# v1_0.net
KiCad netlist of a schematic drawn in EAGLE
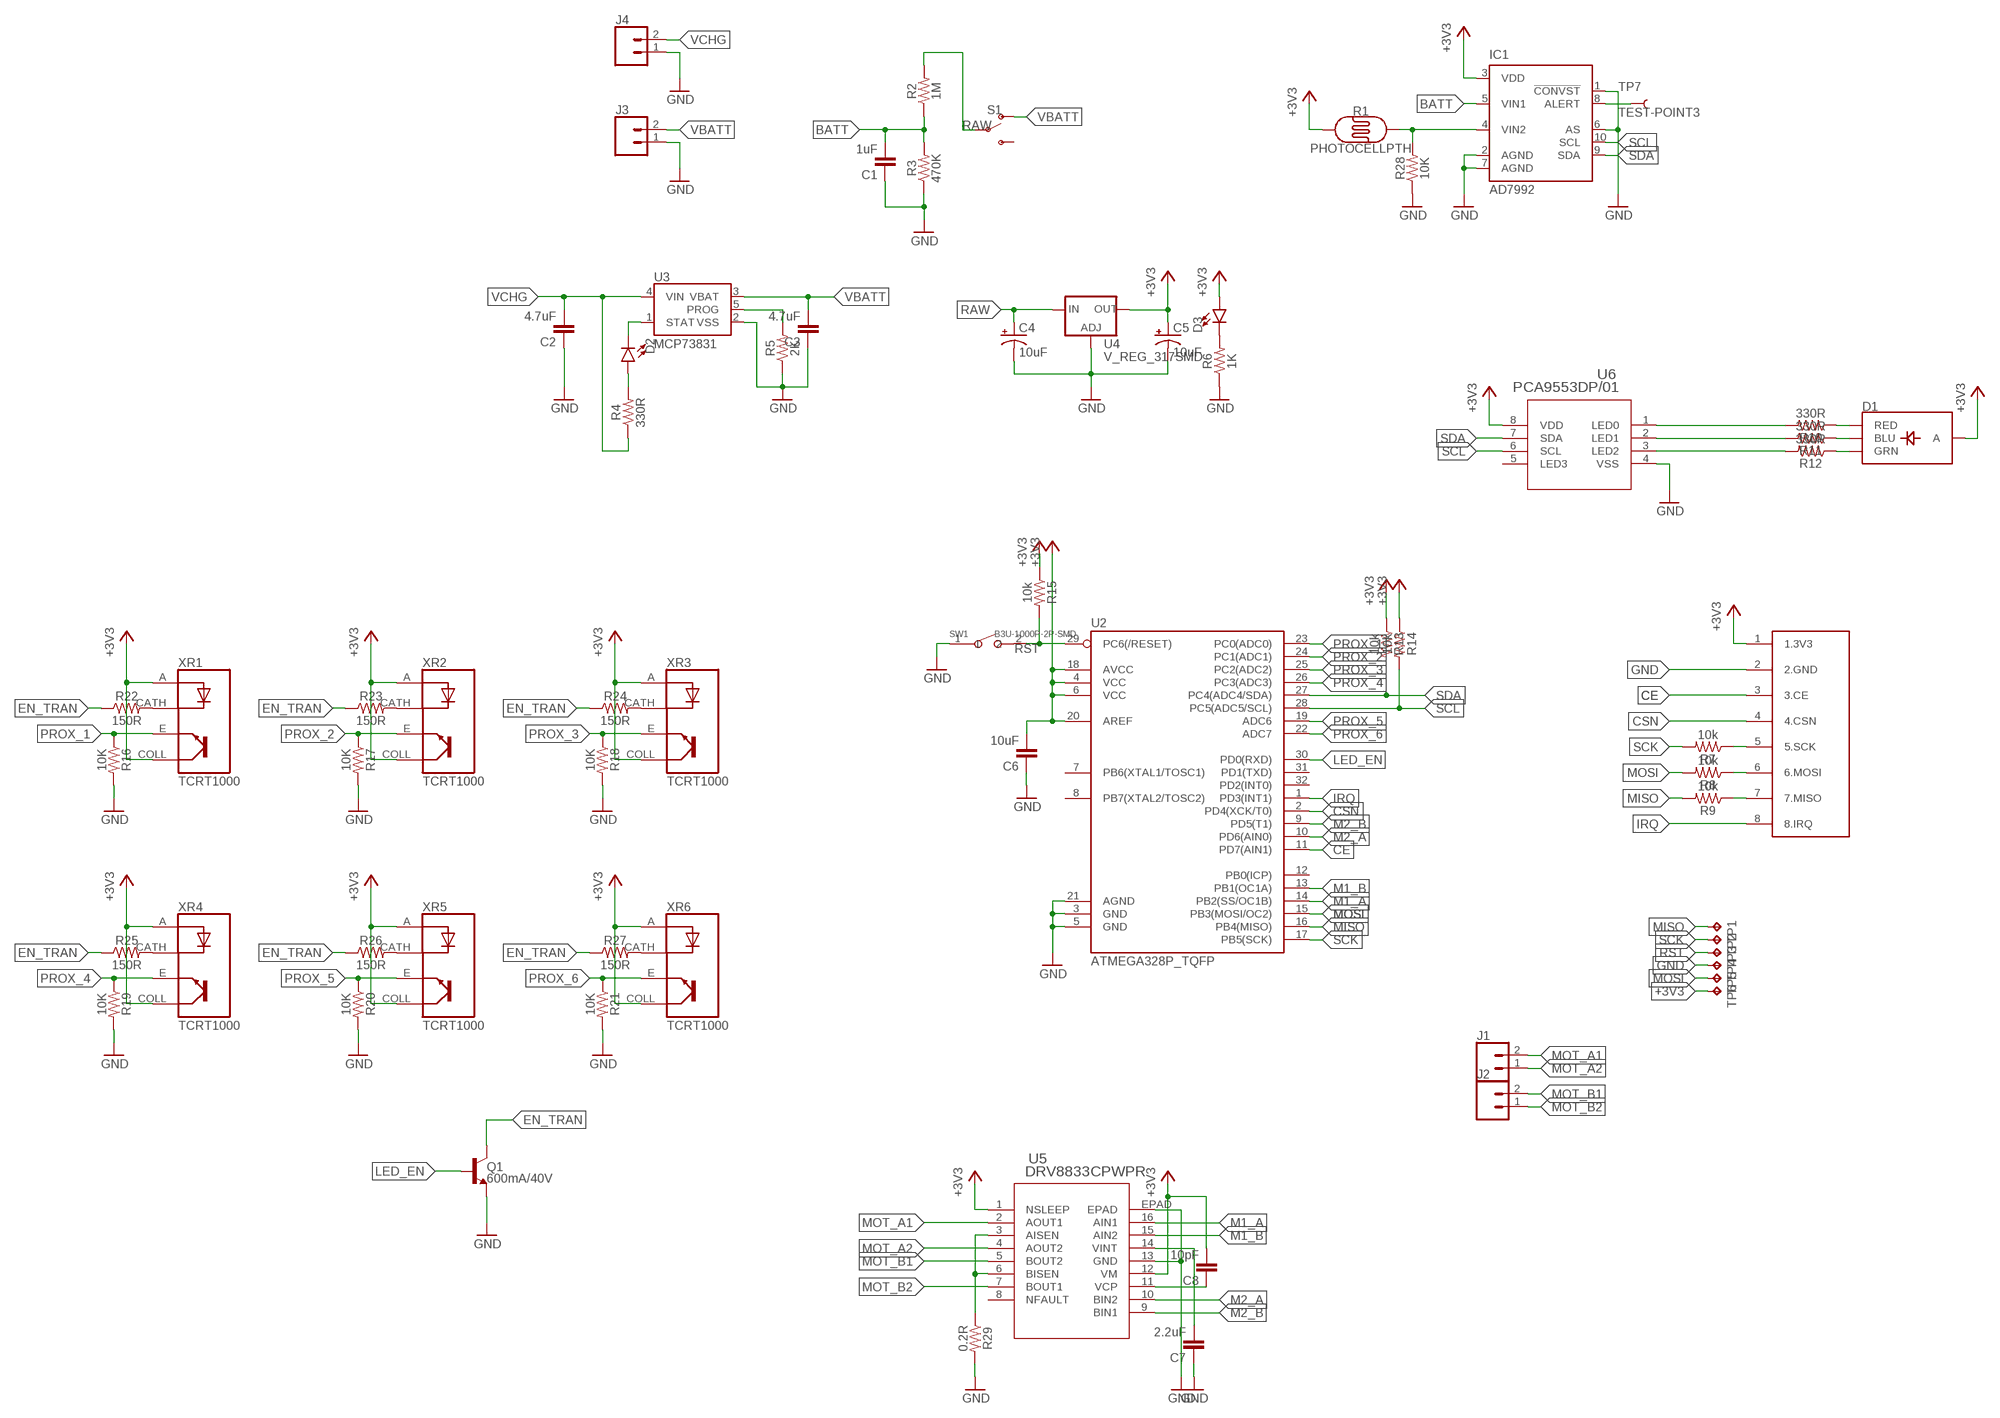
[diagram p0: schematic, sheet 1]

(export (version "E")
  (design (tool "Eeschema 10.0.6"))
  (components
    (comp (ref "C1")
      (value "1uF")
      (footprint "eagle-import:C0603")
      (libsource (lib "eagle-import") (part "C-EUC0603"))
    )
    (comp (ref "C2")
      (value "4.7uF")
      (footprint "eagle-import:C0603")
      (libsource (lib "eagle-import") (part "C-EUC0603"))
    )
    (comp (ref "C3")
      (value "4.7uF")
      (footprint "eagle-import:C0603")
      (libsource (lib "eagle-import") (part "C-EUC0603"))
    )
    (comp (ref "C4")
      (value "10uF")
      (footprint "eagle-import:EIA3216")
      (libsource (lib "eagle-import") (part "10UF-POLAR-EIA3216-16V-10%(TANT)"))
    )
    (comp (ref "C5")
      (value "10uF")
      (footprint "eagle-import:EIA3216")
      (libsource (lib "eagle-import") (part "10UF-POLAR-EIA3216-16V-10%(TANT)"))
    )
    (comp (ref "C6")
      (value "10uF")
      (footprint "eagle-import:C0603")
      (libsource (lib "eagle-import") (part "C-EUC0603"))
    )
    (comp (ref "C7")
      (value "2.2uF")
      (footprint "eagle-import:C0603")
      (libsource (lib "eagle-import") (part "C-EUC0603"))
    )
    (comp (ref "C8")
      (value "10pF")
      (footprint "eagle-import:C0603")
      (libsource (lib "eagle-import") (part "C-EUC0603"))
    )
    (comp (ref "D1")
      (value "LED-RGB-CASMD")
      (footprint "eagle-import:LED-TRICOLOR-SMD")
      (libsource (lib "eagle-import") (part "LED-RGB-CASMD"))
    )
    (comp (ref "D2")
      (value "LED0603")
      (footprint "eagle-import:LED-0603")
      (libsource (lib "eagle-import") (part "LED0603"))
    )
    (comp (ref "D3")
      (value "LED0603")
      (footprint "eagle-import:LED-0603")
      (libsource (lib "eagle-import") (part "LED0603"))
    )
    (comp (ref "IC1")
      (value "AD7992")
      (footprint "eagle-import:MSOP10")
      (fields (field (name "MPN") "AD7992BRMZ-0"))
      (libsource (lib "eagle-import") (part "AD7992"))
    )
    (comp (ref "J1")
      (value "CONN_02")
      (footprint "eagle-import:1X02")
      (libsource (lib "eagle-import") (part "CONN_02"))
    )
    (comp (ref "J2")
      (value "CONN_02")
      (footprint "eagle-import:1X02")
      (libsource (lib "eagle-import") (part "CONN_02"))
    )
    (comp (ref "J3")
      (value "CONN_02")
      (footprint "eagle-import:1X02")
      (libsource (lib "eagle-import") (part "CONN_02"))
    )
    (comp (ref "J4")
      (value "CONN_02")
      (footprint "eagle-import:1X02")
      (libsource (lib "eagle-import") (part "CONN_02"))
    )
    (comp (ref "Q1")
      (value "600mA/40V")
      (footprint "eagle-import:SOT23-3")
      (libsource (lib "eagle-import") (part "TRANS_NPN-MMBT2222AL"))
    )
    (comp (ref "R1")
      (value "PHOTOCELLPTH")
      (footprint "eagle-import:PHOTOCELL")
      (libsource (lib "eagle-import") (part "PHOTOCELLPTH"))
    )
    (comp (ref "R2")
      (value "1M")
      (footprint "eagle-import:0402")
      (libsource (lib "eagle-import") (part "RESISTOR0402"))
    )
    (comp (ref "R3")
      (value "470K")
      (footprint "eagle-import:0402")
      (libsource (lib "eagle-import") (part "RESISTOR0402"))
    )
    (comp (ref "R4")
      (value "330R")
      (footprint "eagle-import:0402")
      (libsource (lib "eagle-import") (part "RESISTOR0402"))
    )
    (comp (ref "R5")
      (value "2K")
      (footprint "eagle-import:0402")
      (libsource (lib "eagle-import") (part "RESISTOR0402"))
    )
    (comp (ref "R6")
      (value "1K")
      (footprint "eagle-import:0402")
      (libsource (lib "eagle-import") (part "RESISTOR0402"))
    )
    (comp (ref "R7")
      (value "10k")
      (footprint "eagle-import:0402")
      (libsource (lib "eagle-import") (part "RESISTOR0402"))
    )
    (comp (ref "R8")
      (value "10k")
      (footprint "eagle-import:0402")
      (libsource (lib "eagle-import") (part "RESISTOR0402"))
    )
    (comp (ref "R9")
      (value "10k")
      (footprint "eagle-import:0402")
      (libsource (lib "eagle-import") (part "RESISTOR0402"))
    )
    (comp (ref "R10")
      (value "330R")
      (footprint "eagle-import:0402")
      (libsource (lib "eagle-import") (part "RESISTOR0402"))
    )
    (comp (ref "R11")
      (value "330R")
      (footprint "eagle-import:0402")
      (libsource (lib "eagle-import") (part "RESISTOR0402"))
    )
    (comp (ref "R12")
      (value "330R")
      (footprint "eagle-import:0402")
      (libsource (lib "eagle-import") (part "RESISTOR0402"))
    )
    (comp (ref "R13")
      (value "10k")
      (footprint "eagle-import:0402")
      (libsource (lib "eagle-import") (part "RESISTOR0402"))
    )
    (comp (ref "R14")
      (value "10k")
      (footprint "eagle-import:0402")
      (libsource (lib "eagle-import") (part "RESISTOR0402"))
    )
    (comp (ref "R15")
      (value "10k")
      (footprint "eagle-import:0402")
      (libsource (lib "eagle-import") (part "RESISTOR0402"))
    )
    (comp (ref "R16")
      (value "10K")
      (footprint "eagle-import:0402")
      (libsource (lib "eagle-import") (part "RESISTOR0402"))
    )
    (comp (ref "R17")
      (value "10K")
      (footprint "eagle-import:0402")
      (libsource (lib "eagle-import") (part "RESISTOR0402"))
    )
    (comp (ref "R18")
      (value "10K")
      (footprint "eagle-import:0402")
      (libsource (lib "eagle-import") (part "RESISTOR0402"))
    )
    (comp (ref "R19")
      (value "10K")
      (footprint "eagle-import:0402")
      (libsource (lib "eagle-import") (part "RESISTOR0402"))
    )
    (comp (ref "R20")
      (value "10K")
      (footprint "eagle-import:0402")
      (libsource (lib "eagle-import") (part "RESISTOR0402"))
    )
    (comp (ref "R21")
      (value "10K")
      (footprint "eagle-import:0402")
      (libsource (lib "eagle-import") (part "RESISTOR0402"))
    )
    (comp (ref "R22")
      (value "150R")
      (footprint "eagle-import:0402")
      (libsource (lib "eagle-import") (part "RESISTOR0402"))
    )
    (comp (ref "R23")
      (value "150R")
      (footprint "eagle-import:0402")
      (libsource (lib "eagle-import") (part "RESISTOR0402"))
    )
    (comp (ref "R24")
      (value "150R")
      (footprint "eagle-import:0402")
      (libsource (lib "eagle-import") (part "RESISTOR0402"))
    )
    (comp (ref "R25")
      (value "150R")
      (footprint "eagle-import:0402")
      (libsource (lib "eagle-import") (part "RESISTOR0402"))
    )
    (comp (ref "R26")
      (value "150R")
      (footprint "eagle-import:0402")
      (libsource (lib "eagle-import") (part "RESISTOR0402"))
    )
    (comp (ref "R27")
      (value "150R")
      (footprint "eagle-import:0402")
      (libsource (lib "eagle-import") (part "RESISTOR0402"))
    )
    (comp (ref "R28")
      (value "10K")
      (footprint "eagle-import:0402")
      (libsource (lib "eagle-import") (part "RESISTOR0402"))
    )
    (comp (ref "R29")
      (value "0.2R")
      (footprint "eagle-import:0402")
      (libsource (lib "eagle-import") (part "RESISTOR0402"))
    )
    (comp (ref "S1")
      (value "SWITCH-SPDT-SMD-RIGHT-ANGLE")
      (footprint "eagle-import:SWITCH_SPST_SMD_A")
      (libsource (lib "eagle-import") (part "SWITCH-SPDT-SMD-RIGHT-ANGLE"))
    )
    (comp (ref "SW1")
      (value "B3U-1000P-2P-SMD")
      (footprint "eagle-import:SW2-2.6-3.0X2.5X1.2+0.4MM")
      (libsource (lib "eagle-import") (part "SMD-BUTTON(2P-3.0X2.5X1.2+0.4MM)-B3U-1000P-2P-SMD"))
    )
    (comp (ref "TP1")
      (value "TPB1,27")
      (footprint "eagle-import:B1,27")
      (libsource (lib "eagle-import") (part "TPB1,27"))
    )
    (comp (ref "TP2")
      (value "TPB1,27")
      (footprint "eagle-import:B1,27")
      (libsource (lib "eagle-import") (part "TPB1,27"))
    )
    (comp (ref "TP3")
      (value "TPB1,27")
      (footprint "eagle-import:B1,27")
      (libsource (lib "eagle-import") (part "TPB1,27"))
    )
    (comp (ref "TP4")
      (value "TPB1,27")
      (footprint "eagle-import:B1,27")
      (libsource (lib "eagle-import") (part "TPB1,27"))
    )
    (comp (ref "TP5")
      (value "TPB1,27")
      (footprint "eagle-import:B1,27")
      (libsource (lib "eagle-import") (part "TPB1,27"))
    )
    (comp (ref "TP6")
      (value "TPB1,27")
      (footprint "eagle-import:B1,27")
      (libsource (lib "eagle-import") (part "TPB1,27"))
    )
    (comp (ref "TP7")
      (value "TEST-POINT3")
      (footprint "eagle-import:PAD.03X.03")
      (libsource (lib "eagle-import") (part "TEST-POINT3"))
    )
    (comp (ref "U$1")
      (value "NRF24L01+")
      (footprint "eagle-import:NRF24L01+")
      (libsource (lib "eagle-import") (part "NRF24L01+"))
    )
    (comp (ref "U2")
      (value "ATMEGA328P_TQFP")
      (footprint "eagle-import:TQFP32-08")
      (libsource (lib "eagle-import") (part "ATMEGA328P_TQFP"))
    )
    (comp (ref "U3")
      (value "MCP73831")
      (footprint "eagle-import:SOT23-5")
      (libsource (lib "eagle-import") (part "MCP73831"))
    )
    (comp (ref "U4")
      (value "V_REG_317SMD")
      (footprint "eagle-import:SOT223")
      (libsource (lib "eagle-import") (part "V_REG_317SMD"))
    )
    (comp (ref "U5")
      (value "DRV8833CPWPR")
      (footprint "eagle-import:PWP16_2P31X2P46")
      (libsource (lib "eagle-import") (part "DRV8833CPWPR"))
    )
    (comp (ref "U6")
      (value "PCA9553DP/01")
      (footprint "eagle-import:SOT505-1")
      (fields (field (name "MANUFACTURER_PART_NUMBER") "PCA9553DP01"))
      (libsource (lib "eagle-import") (part "PCA9553DP/01"))
    )
    (comp (ref "XR1")
      (value "TCRT1000")
      (footprint "eagle-import:XDCR_TCRT1000")
      (fields (field (name "MF") "Vishay"))
      (libsource (lib "eagle-import") (part "TCRT1000"))
    )
    (comp (ref "XR2")
      (value "TCRT1000")
      (footprint "eagle-import:XDCR_TCRT1000")
      (fields (field (name "MF") "Vishay"))
      (libsource (lib "eagle-import") (part "TCRT1000"))
    )
    (comp (ref "XR3")
      (value "TCRT1000")
      (footprint "eagle-import:XDCR_TCRT1000")
      (fields (field (name "MF") "Vishay"))
      (libsource (lib "eagle-import") (part "TCRT1000"))
    )
    (comp (ref "XR4")
      (value "TCRT1000")
      (footprint "eagle-import:XDCR_TCRT1000")
      (fields (field (name "MF") "Vishay"))
      (libsource (lib "eagle-import") (part "TCRT1000"))
    )
    (comp (ref "XR5")
      (value "TCRT1000")
      (footprint "eagle-import:XDCR_TCRT1000")
      (fields (field (name "MF") "Vishay"))
      (libsource (lib "eagle-import") (part "TCRT1000"))
    )
    (comp (ref "XR6")
      (value "TCRT1000")
      (footprint "eagle-import:XDCR_TCRT1000")
      (fields (field (name "MF") "Vishay"))
      (libsource (lib "eagle-import") (part "TCRT1000"))
    )
  )
  (nets
    (net (code "1") (name "+3V3") (class "Default")
      (node (ref "C5") (pin "+") (pinfunction "+_+") (pintype "passive"))
      (node (ref "C6") (pin "2") (pinfunction "2_2") (pintype "passive"))
      (node (ref "C8") (pin "2") (pinfunction "2_2") (pintype "passive"))
      (node (ref "D1") (pin "A") (pinfunction "A_A") (pintype "bidirectional"))
      (node (ref "D3") (pin "A") (pinfunction "A_A") (pintype "passive"))
      (node (ref "IC1") (pin "3") (pinfunction "VDD_3") (pintype "power_in"))
      (node (ref "R1") (pin "1") (pinfunction "P$1_1") (pintype "bidirectional"))
      (node (ref "R13") (pin "1") (pinfunction "1_1") (pintype "passive"))
      (node (ref "R14") (pin "1") (pinfunction "1_1") (pintype "passive"))
      (node (ref "R15") (pin "1") (pinfunction "1_1") (pintype "passive"))
      (node (ref "TP6") (pin "TP") (pinfunction "TP_TP") (pintype "input"))
      (node (ref "U$1") (pin "1") (pinfunction "1.3V3_1") (pintype "bidirectional"))
      (node (ref "U2") (pin "18") (pinfunction "AVCC_18") (pintype "bidirectional"))
      (node (ref "U2") (pin "20") (pinfunction "AREF_20") (pintype "bidirectional"))
      (node (ref "U2") (pin "4") (pinfunction "VCC_4") (pintype "bidirectional"))
      (node (ref "U2") (pin "6") (pinfunction "VCC_6") (pintype "bidirectional"))
      (node (ref "U4") (pin "2") (pinfunction "OUT_2") (pintype "output"))
      (node (ref "U5") (pin "1") (pinfunction "NSLEEP_1") (pintype "input"))
      (node (ref "U5") (pin "12") (pinfunction "VM_12") (pintype "power_in"))
      (node (ref "U6") (pin "8") (pinfunction "VDD_8") (pintype "passive"))
      (node (ref "XR1") (pin "A") (pinfunction "A_A") (pintype "passive"))
      (node (ref "XR1") (pin "COLL") (pinfunction "CO_COLL") (pintype "passive"))
      (node (ref "XR2") (pin "A") (pinfunction "A_A") (pintype "passive"))
      (node (ref "XR2") (pin "COLL") (pinfunction "CO_COLL") (pintype "passive"))
      (node (ref "XR3") (pin "A") (pinfunction "A_A") (pintype "passive"))
      (node (ref "XR3") (pin "COLL") (pinfunction "CO_COLL") (pintype "passive"))
      (node (ref "XR4") (pin "A") (pinfunction "A_A") (pintype "passive"))
      (node (ref "XR4") (pin "COLL") (pinfunction "CO_COLL") (pintype "passive"))
      (node (ref "XR5") (pin "A") (pinfunction "A_A") (pintype "passive"))
      (node (ref "XR5") (pin "COLL") (pinfunction "CO_COLL") (pintype "passive"))
      (node (ref "XR6") (pin "A") (pinfunction "A_A") (pintype "passive"))
      (node (ref "XR6") (pin "COLL") (pinfunction "CO_COLL") (pintype "passive"))
    )
    (net (code "2") (name "BATT") (class "Default")
      (node (ref "C1") (pin "2") (pinfunction "2_2") (pintype "passive"))
      (node (ref "IC1") (pin "5") (pinfunction "VIN1_5") (pintype "input"))
      (node (ref "R2") (pin "1") (pinfunction "1_1") (pintype "passive"))
      (node (ref "R3") (pin "2") (pinfunction "2_2") (pintype "passive"))
    )
    (net (code "3") (name "CE") (class "Default")
      (node (ref "U$1") (pin "3") (pinfunction "3.CE_3") (pintype "bidirectional"))
      (node (ref "U2") (pin "11") (pinfunction "PD7(AIN1)_11") (pintype "bidirectional"))
    )
    (net (code "4") (name "CSN") (class "Default")
      (node (ref "U$1") (pin "4") (pinfunction "4.CSN_4") (pintype "bidirectional"))
      (node (ref "U2") (pin "2") (pinfunction "PD4(XCK/T0)_2") (pintype "bidirectional"))
    )
    (net (code "5") (name "EN_TRAN") (class "Default")
      (node (ref "Q1") (pin "3") (pinfunction "C_3") (pintype "passive"))
      (node (ref "R22") (pin "1") (pinfunction "1_1") (pintype "passive"))
      (node (ref "R23") (pin "1") (pinfunction "1_1") (pintype "passive"))
      (node (ref "R24") (pin "1") (pinfunction "1_1") (pintype "passive"))
      (node (ref "R25") (pin "1") (pinfunction "1_1") (pintype "passive"))
      (node (ref "R26") (pin "1") (pinfunction "1_1") (pintype "passive"))
      (node (ref "R27") (pin "1") (pinfunction "1_1") (pintype "passive"))
    )
    (net (code "6") (name "GND") (class "Default")
      (node (ref "C1") (pin "1") (pinfunction "1_1") (pintype "passive"))
      (node (ref "C2") (pin "1") (pinfunction "1_1") (pintype "passive"))
      (node (ref "C3") (pin "1") (pinfunction "1_1") (pintype "passive"))
      (node (ref "C4") (pin "-") (pinfunction "-_-") (pintype "passive"))
      (node (ref "C5") (pin "-") (pinfunction "-_-") (pintype "passive"))
      (node (ref "C6") (pin "1") (pinfunction "1_1") (pintype "passive"))
      (node (ref "C7") (pin "1") (pinfunction "1_1") (pintype "passive"))
      (node (ref "IC1") (pin "1") (pinfunction "~{CONVST}_1") (pintype "input"))
      (node (ref "IC1") (pin "2") (pinfunction "AGND_2") (pintype "power_in"))
      (node (ref "IC1") (pin "6") (pinfunction "AS_6") (pintype "input"))
      (node (ref "IC1") (pin "7") (pinfunction "AGND_7") (pintype "power_in"))
      (node (ref "J3") (pin "1") (pinfunction "1_1") (pintype "passive"))
      (node (ref "J4") (pin "1") (pinfunction "1_1") (pintype "passive"))
      (node (ref "Q1") (pin "2") (pinfunction "E_2") (pintype "passive"))
      (node (ref "R16") (pin "2") (pinfunction "2_2") (pintype "passive"))
      (node (ref "R17") (pin "2") (pinfunction "2_2") (pintype "passive"))
      (node (ref "R18") (pin "2") (pinfunction "2_2") (pintype "passive"))
      (node (ref "R19") (pin "2") (pinfunction "2_2") (pintype "passive"))
      (node (ref "R20") (pin "2") (pinfunction "2_2") (pintype "passive"))
      (node (ref "R21") (pin "2") (pinfunction "2_2") (pintype "passive"))
      (node (ref "R28") (pin "1") (pinfunction "1_1") (pintype "passive"))
      (node (ref "R29") (pin "2") (pinfunction "2_2") (pintype "passive"))
      (node (ref "R3") (pin "1") (pinfunction "1_1") (pintype "passive"))
      (node (ref "R5") (pin "1") (pinfunction "1_1") (pintype "passive"))
      (node (ref "R6") (pin "1") (pinfunction "1_1") (pintype "passive"))
      (node (ref "SW1") (pin "1") (pinfunction "1_1") (pintype "bidirectional"))
      (node (ref "TP4") (pin "TP") (pinfunction "TP_TP") (pintype "input"))
      (node (ref "U$1") (pin "2") (pinfunction "2.GND_2") (pintype "bidirectional"))
      (node (ref "U2") (pin "21") (pinfunction "AGND_21") (pintype "bidirectional"))
      (node (ref "U2") (pin "3") (pinfunction "GND_3") (pintype "bidirectional"))
      (node (ref "U2") (pin "5") (pinfunction "GND_5") (pintype "bidirectional"))
      (node (ref "U3") (pin "2") (pinfunction "VSS_2") (pintype "power_in"))
      (node (ref "U4") (pin "1") (pinfunction "ADJ_1") (pintype "input"))
      (node (ref "U5") (pin "13") (pinfunction "GND_13") (pintype "power_in"))
      (node (ref "U5") (pin "EPAD") (pinfunction "EPAD_EPAD") (pintype "passive"))
      (node (ref "U6") (pin "4") (pinfunction "VSS_4") (pintype "passive"))
    )
    (net (code "7") (name "IRQ") (class "Default")
      (node (ref "U$1") (pin "8") (pinfunction "8.IRQ_8") (pintype "bidirectional"))
      (node (ref "U2") (pin "1") (pinfunction "PD3(INT1)_1") (pintype "bidirectional"))
    )
    (net (code "8") (name "LED_EN") (class "Default")
      (node (ref "Q1") (pin "1") (pinfunction "B_1") (pintype "passive"))
      (node (ref "U2") (pin "30") (pinfunction "PD0(RXD)_30") (pintype "bidirectional"))
    )
    (net (code "9") (name "M1_A") (class "Default")
      (node (ref "U2") (pin "14") (pinfunction "PB2(SS/OC1B)_14") (pintype "bidirectional"))
      (node (ref "U5") (pin "16") (pinfunction "AIN1_16") (pintype "input"))
    )
    (net (code "10") (name "M1_B") (class "Default")
      (node (ref "U2") (pin "13") (pinfunction "PB1(OC1A)_13") (pintype "bidirectional"))
      (node (ref "U5") (pin "15") (pinfunction "AIN2_15") (pintype "input"))
    )
    (net (code "11") (name "M2_A") (class "Default")
      (node (ref "U2") (pin "10") (pinfunction "PD6(AIN0)_10") (pintype "bidirectional"))
      (node (ref "U5") (pin "10") (pinfunction "BIN2_10") (pintype "input"))
    )
    (net (code "12") (name "M2_B") (class "Default")
      (node (ref "U2") (pin "9") (pinfunction "PD5(T1)_9") (pintype "bidirectional"))
      (node (ref "U5") (pin "9") (pinfunction "BIN1_9") (pintype "input"))
    )
    (net (code "13") (name "MISO") (class "Default")
      (node (ref "R9") (pin "2") (pinfunction "2_2") (pintype "passive"))
      (node (ref "TP1") (pin "TP") (pinfunction "TP_TP") (pintype "input"))
      (node (ref "U2") (pin "16") (pinfunction "PB4(MISO)_16") (pintype "bidirectional"))
    )
    (net (code "14") (name "MOSI") (class "Default")
      (node (ref "R8") (pin "2") (pinfunction "2_2") (pintype "passive"))
      (node (ref "TP5") (pin "TP") (pinfunction "TP_TP") (pintype "input"))
      (node (ref "U2") (pin "15") (pinfunction "PB3(MOSI/OC2)_15") (pintype "bidirectional"))
    )
    (net (code "15") (name "MOT_A1") (class "Default")
      (node (ref "J1") (pin "2") (pinfunction "2_2") (pintype "passive"))
      (node (ref "U5") (pin "2") (pinfunction "AOUT1_2") (pintype "output"))
    )
    (net (code "16") (name "MOT_A2") (class "Default")
      (node (ref "J1") (pin "1") (pinfunction "1_1") (pintype "passive"))
      (node (ref "U5") (pin "4") (pinfunction "AOUT2_4") (pintype "output"))
    )
    (net (code "17") (name "MOT_B1") (class "Default")
      (node (ref "J2") (pin "2") (pinfunction "2_2") (pintype "passive"))
      (node (ref "U5") (pin "5") (pinfunction "BOUT2_5") (pintype "output"))
    )
    (net (code "18") (name "MOT_B2") (class "Default")
      (node (ref "J2") (pin "1") (pinfunction "1_1") (pintype "passive"))
      (node (ref "U5") (pin "7") (pinfunction "BOUT1_7") (pintype "output"))
    )
    (net (code "19") (name "Net-(D1-BLU)") (class "Default")
      (node (ref "D1") (pin "B") (pinfunction "BLU_B") (pintype "bidirectional"))
      (node (ref "R11") (pin "1") (pinfunction "1_1") (pintype "passive"))
    )
    (net (code "20") (name "Net-(D1-GRN)") (class "Default")
      (node (ref "D1") (pin "G") (pinfunction "GRN_G") (pintype "bidirectional"))
      (node (ref "R12") (pin "1") (pinfunction "1_1") (pintype "passive"))
    )
    (net (code "21") (name "Net-(D1-RED)") (class "Default")
      (node (ref "D1") (pin "R") (pinfunction "RED_R") (pintype "bidirectional"))
      (node (ref "R10") (pin "1") (pinfunction "1_1") (pintype "passive"))
    )
    (net (code "22") (name "Net-(D2-PadA)") (class "Default")
      (node (ref "D2") (pin "A") (pinfunction "A_A") (pintype "passive"))
      (node (ref "R4") (pin "2") (pinfunction "2_2") (pintype "passive"))
    )
    (net (code "23") (name "Net-(D3-PadC)") (class "Default")
      (node (ref "D3") (pin "C") (pinfunction "C_C") (pintype "passive"))
      (node (ref "R6") (pin "2") (pinfunction "2_2") (pintype "passive"))
    )
    (net (code "24") (name "Net-(IC1-ALERT)") (class "Default")
      (node (ref "IC1") (pin "8") (pinfunction "ALERT_8") (pintype "output"))
      (node (ref "TP7") (pin "P$1") (pinfunction "1_P$1") (pintype "bidirectional"))
    )
    (net (code "25") (name "Net-(IC1-VIN2)") (class "Default")
      (node (ref "IC1") (pin "4") (pinfunction "VIN2_4") (pintype "input"))
      (node (ref "R1") (pin "2") (pinfunction "P$2_2") (pintype "bidirectional"))
      (node (ref "R28") (pin "2") (pinfunction "2_2") (pintype "passive"))
    )
    (net (code "26") (name "Net-(U$1-5.SCK)") (class "Default")
      (node (ref "R7") (pin "1") (pinfunction "1_1") (pintype "passive"))
      (node (ref "U$1") (pin "5") (pinfunction "5.SCK_5") (pintype "bidirectional"))
    )
    (net (code "27") (name "Net-(U$1-6.MOSI)") (class "Default")
      (node (ref "R8") (pin "1") (pinfunction "1_1") (pintype "passive"))
      (node (ref "U$1") (pin "6") (pinfunction "6.MOSI_6") (pintype "bidirectional"))
    )
    (net (code "28") (name "Net-(U$1-7.MISO)") (class "Default")
      (node (ref "R9") (pin "1") (pinfunction "1_1") (pintype "passive"))
      (node (ref "U$1") (pin "7") (pinfunction "7.MISO_7") (pintype "bidirectional"))
    )
    (net (code "29") (name "Net-(U3-PROG)") (class "Default")
      (node (ref "R5") (pin "2") (pinfunction "2_2") (pintype "passive"))
      (node (ref "U3") (pin "5") (pinfunction "PROG_5") (pintype "input"))
    )
    (net (code "30") (name "Net-(U3-STAT)") (class "Default")
      (node (ref "D2") (pin "C") (pinfunction "C_C") (pintype "passive"))
      (node (ref "U3") (pin "1") (pinfunction "STAT_1") (pintype "output"))
    )
    (net (code "31") (name "Net-(U5-AISEN)") (class "Default")
      (node (ref "R29") (pin "1") (pinfunction "1_1") (pintype "passive"))
      (node (ref "U5") (pin "3") (pinfunction "AISEN_3") (pintype "bidirectional"))
      (node (ref "U5") (pin "6") (pinfunction "BISEN_6") (pintype "bidirectional"))
    )
    (net (code "32") (name "Net-(U5-VCP)") (class "Default")
      (node (ref "C8") (pin "1") (pinfunction "1_1") (pintype "passive"))
      (node (ref "U5") (pin "11") (pinfunction "VCP_11") (pintype "bidirectional"))
    )
    (net (code "33") (name "Net-(U5-VINT)") (class "Default")
      (node (ref "C7") (pin "2") (pinfunction "2_2") (pintype "passive"))
      (node (ref "U5") (pin "14") (pinfunction "VINT_14") (pintype "power_in"))
    )
    (net (code "34") (name "Net-(U6-LED0)") (class "Default")
      (node (ref "R10") (pin "2") (pinfunction "2_2") (pintype "passive"))
      (node (ref "U6") (pin "1") (pinfunction "LED0_1") (pintype "passive"))
    )
    (net (code "35") (name "Net-(U6-LED1)") (class "Default")
      (node (ref "R11") (pin "2") (pinfunction "2_2") (pintype "passive"))
      (node (ref "U6") (pin "2") (pinfunction "LED1_2") (pintype "passive"))
    )
    (net (code "36") (name "Net-(U6-LED2)") (class "Default")
      (node (ref "R12") (pin "2") (pinfunction "2_2") (pintype "passive"))
      (node (ref "U6") (pin "3") (pinfunction "LED2_3") (pintype "passive"))
    )
    (net (code "37") (name "Net-(XR1-C)") (class "Default")
      (node (ref "R22") (pin "2") (pinfunction "2_2") (pintype "passive"))
      (node (ref "XR1") (pin "CATH") (pinfunction "C_CATH") (pintype "passive"))
    )
    (net (code "38") (name "Net-(XR2-C)") (class "Default")
      (node (ref "R23") (pin "2") (pinfunction "2_2") (pintype "passive"))
      (node (ref "XR2") (pin "CATH") (pinfunction "C_CATH") (pintype "passive"))
    )
    (net (code "39") (name "Net-(XR3-C)") (class "Default")
      (node (ref "R24") (pin "2") (pinfunction "2_2") (pintype "passive"))
      (node (ref "XR3") (pin "CATH") (pinfunction "C_CATH") (pintype "passive"))
    )
    (net (code "40") (name "Net-(XR4-C)") (class "Default")
      (node (ref "R25") (pin "2") (pinfunction "2_2") (pintype "passive"))
      (node (ref "XR4") (pin "CATH") (pinfunction "C_CATH") (pintype "passive"))
    )
    (net (code "41") (name "Net-(XR5-C)") (class "Default")
      (node (ref "R26") (pin "2") (pinfunction "2_2") (pintype "passive"))
      (node (ref "XR5") (pin "CATH") (pinfunction "C_CATH") (pintype "passive"))
    )
    (net (code "42") (name "Net-(XR6-C)") (class "Default")
      (node (ref "R27") (pin "2") (pinfunction "2_2") (pintype "passive"))
      (node (ref "XR6") (pin "CATH") (pinfunction "C_CATH") (pintype "passive"))
    )
    (net (code "43") (name "PROX_1") (class "Default")
      (node (ref "R16") (pin "1") (pinfunction "1_1") (pintype "passive"))
      (node (ref "U2") (pin "23") (pinfunction "PC0(ADC0)_23") (pintype "bidirectional"))
      (node (ref "XR1") (pin "E") (pinfunction "E_E") (pintype "passive"))
    )
    (net (code "44") (name "PROX_2") (class "Default")
      (node (ref "R17") (pin "1") (pinfunction "1_1") (pintype "passive"))
      (node (ref "U2") (pin "24") (pinfunction "PC1(ADC1)_24") (pintype "bidirectional"))
      (node (ref "XR2") (pin "E") (pinfunction "E_E") (pintype "passive"))
    )
    (net (code "45") (name "PROX_3") (class "Default")
      (node (ref "R18") (pin "1") (pinfunction "1_1") (pintype "passive"))
      (node (ref "U2") (pin "25") (pinfunction "PC2(ADC2)_25") (pintype "bidirectional"))
      (node (ref "XR3") (pin "E") (pinfunction "E_E") (pintype "passive"))
    )
    (net (code "46") (name "PROX_4") (class "Default")
      (node (ref "R19") (pin "1") (pinfunction "1_1") (pintype "passive"))
      (node (ref "U2") (pin "26") (pinfunction "PC3(ADC3)_26") (pintype "bidirectional"))
      (node (ref "XR4") (pin "E") (pinfunction "E_E") (pintype "passive"))
    )
    (net (code "47") (name "PROX_5") (class "Default")
      (node (ref "R20") (pin "1") (pinfunction "1_1") (pintype "passive"))
      (node (ref "U2") (pin "19") (pinfunction "ADC6_19") (pintype "bidirectional"))
      (node (ref "XR5") (pin "E") (pinfunction "E_E") (pintype "passive"))
    )
    (net (code "48") (name "PROX_6") (class "Default")
      (node (ref "R21") (pin "1") (pinfunction "1_1") (pintype "passive"))
      (node (ref "U2") (pin "22") (pinfunction "ADC7_22") (pintype "bidirectional"))
      (node (ref "XR6") (pin "E") (pinfunction "E_E") (pintype "passive"))
    )
    (net (code "49") (name "RAW") (class "Default")
      (node (ref "C4") (pin "+") (pinfunction "+_+") (pintype "passive"))
      (node (ref "R2") (pin "2") (pinfunction "2_2") (pintype "passive"))
      (node (ref "S1") (pin "2") (pinfunction "P_2") (pintype "passive"))
      (node (ref "U4") (pin "3") (pinfunction "IN_3") (pintype "input"))
    )
    (net (code "50") (name "RST") (class "Default")
      (node (ref "R15") (pin "2") (pinfunction "2_2") (pintype "passive"))
      (node (ref "SW1") (pin "2") (pinfunction "2_2") (pintype "bidirectional"))
      (node (ref "TP3") (pin "TP") (pinfunction "TP_TP") (pintype "input"))
      (node (ref "U2") (pin "29") (pinfunction "PC6(/RESET)_29") (pintype "bidirectional"))
    )
    (net (code "51") (name "SCK") (class "Default")
      (node (ref "R7") (pin "2") (pinfunction "2_2") (pintype "passive"))
      (node (ref "TP2") (pin "TP") (pinfunction "TP_TP") (pintype "input"))
      (node (ref "U2") (pin "17") (pinfunction "PB5(SCK)_17") (pintype "bidirectional"))
    )
    (net (code "52") (name "SCL") (class "Default")
      (node (ref "IC1") (pin "10") (pinfunction "SCL_10") (pintype "input"))
      (node (ref "R14") (pin "2") (pinfunction "2_2") (pintype "passive"))
      (node (ref "U2") (pin "28") (pinfunction "PC5(ADC5/SCL)_28") (pintype "bidirectional"))
      (node (ref "U6") (pin "6") (pinfunction "SCL_6") (pintype "passive"))
    )
    (net (code "53") (name "SDA") (class "Default")
      (node (ref "IC1") (pin "9") (pinfunction "SDA_9") (pintype "bidirectional"))
      (node (ref "R13") (pin "2") (pinfunction "2_2") (pintype "passive"))
      (node (ref "U2") (pin "27") (pinfunction "PC4(ADC4/SDA)_27") (pintype "bidirectional"))
      (node (ref "U6") (pin "7") (pinfunction "SDA_7") (pintype "passive"))
    )
    (net (code "54") (name "VBATT") (class "Default")
      (node (ref "C3") (pin "2") (pinfunction "2_2") (pintype "passive"))
      (node (ref "J3") (pin "2") (pinfunction "2_2") (pintype "passive"))
      (node (ref "S1") (pin "1") (pinfunction "O_1") (pintype "passive"))
      (node (ref "U3") (pin "3") (pinfunction "VBAT_3") (pintype "power_in"))
    )
    (net (code "55") (name "VCHG") (class "Default")
      (node (ref "C2") (pin "2") (pinfunction "2_2") (pintype "passive"))
      (node (ref "J4") (pin "2") (pinfunction "2_2") (pintype "passive"))
      (node (ref "R4") (pin "1") (pinfunction "1_1") (pintype "passive"))
      (node (ref "U3") (pin "4") (pinfunction "VIN_4") (pintype "power_in"))
    )
    (net (code "56") (name "unconnected-(S1-S-Pad3)") (class "Default")
      (node (ref "S1") (pin "3") (pinfunction "S_3") (pintype "passive"))
    )
    (net (code "57") (name "unconnected-(U2-PB0(ICP)-Pad12)") (class "Default")
      (node (ref "U2") (pin "12") (pinfunction "PB0(ICP)_12") (pintype "bidirectional"))
    )
    (net (code "58") (name "unconnected-(U2-PB6(XTAL1{slash}TOSC1)-Pad7)") (class "Default")
      (node (ref "U2") (pin "7") (pinfunction "PB6(XTAL1/TOSC1)_7") (pintype "bidirectional"))
    )
    (net (code "59") (name "unconnected-(U2-PB7(XTAL2{slash}TOSC2)-Pad8)") (class "Default")
      (node (ref "U2") (pin "8") (pinfunction "PB7(XTAL2/TOSC2)_8") (pintype "bidirectional"))
    )
    (net (code "60") (name "unconnected-(U2-PD1(TXD)-Pad31)") (class "Default")
      (node (ref "U2") (pin "31") (pinfunction "PD1(TXD)_31") (pintype "bidirectional"))
    )
    (net (code "61") (name "unconnected-(U2-PD2(INT0)-Pad32)") (class "Default")
      (node (ref "U2") (pin "32") (pinfunction "PD2(INT0)_32") (pintype "bidirectional"))
    )
    (net (code "62") (name "unconnected-(U5-NFAULT-Pad8)") (class "Default")
      (node (ref "U5") (pin "8") (pinfunction "NFAULT_8") (pintype "output"))
    )
    (net (code "63") (name "unconnected-(U6-LED3-Pad5)") (class "Default")
      (node (ref "U6") (pin "5") (pinfunction "LED3_5") (pintype "passive"))
    )
  )
)
